# 5V-3_3VSupply_USB.net
KiCad netlist of a schematic drawn in EAGLE
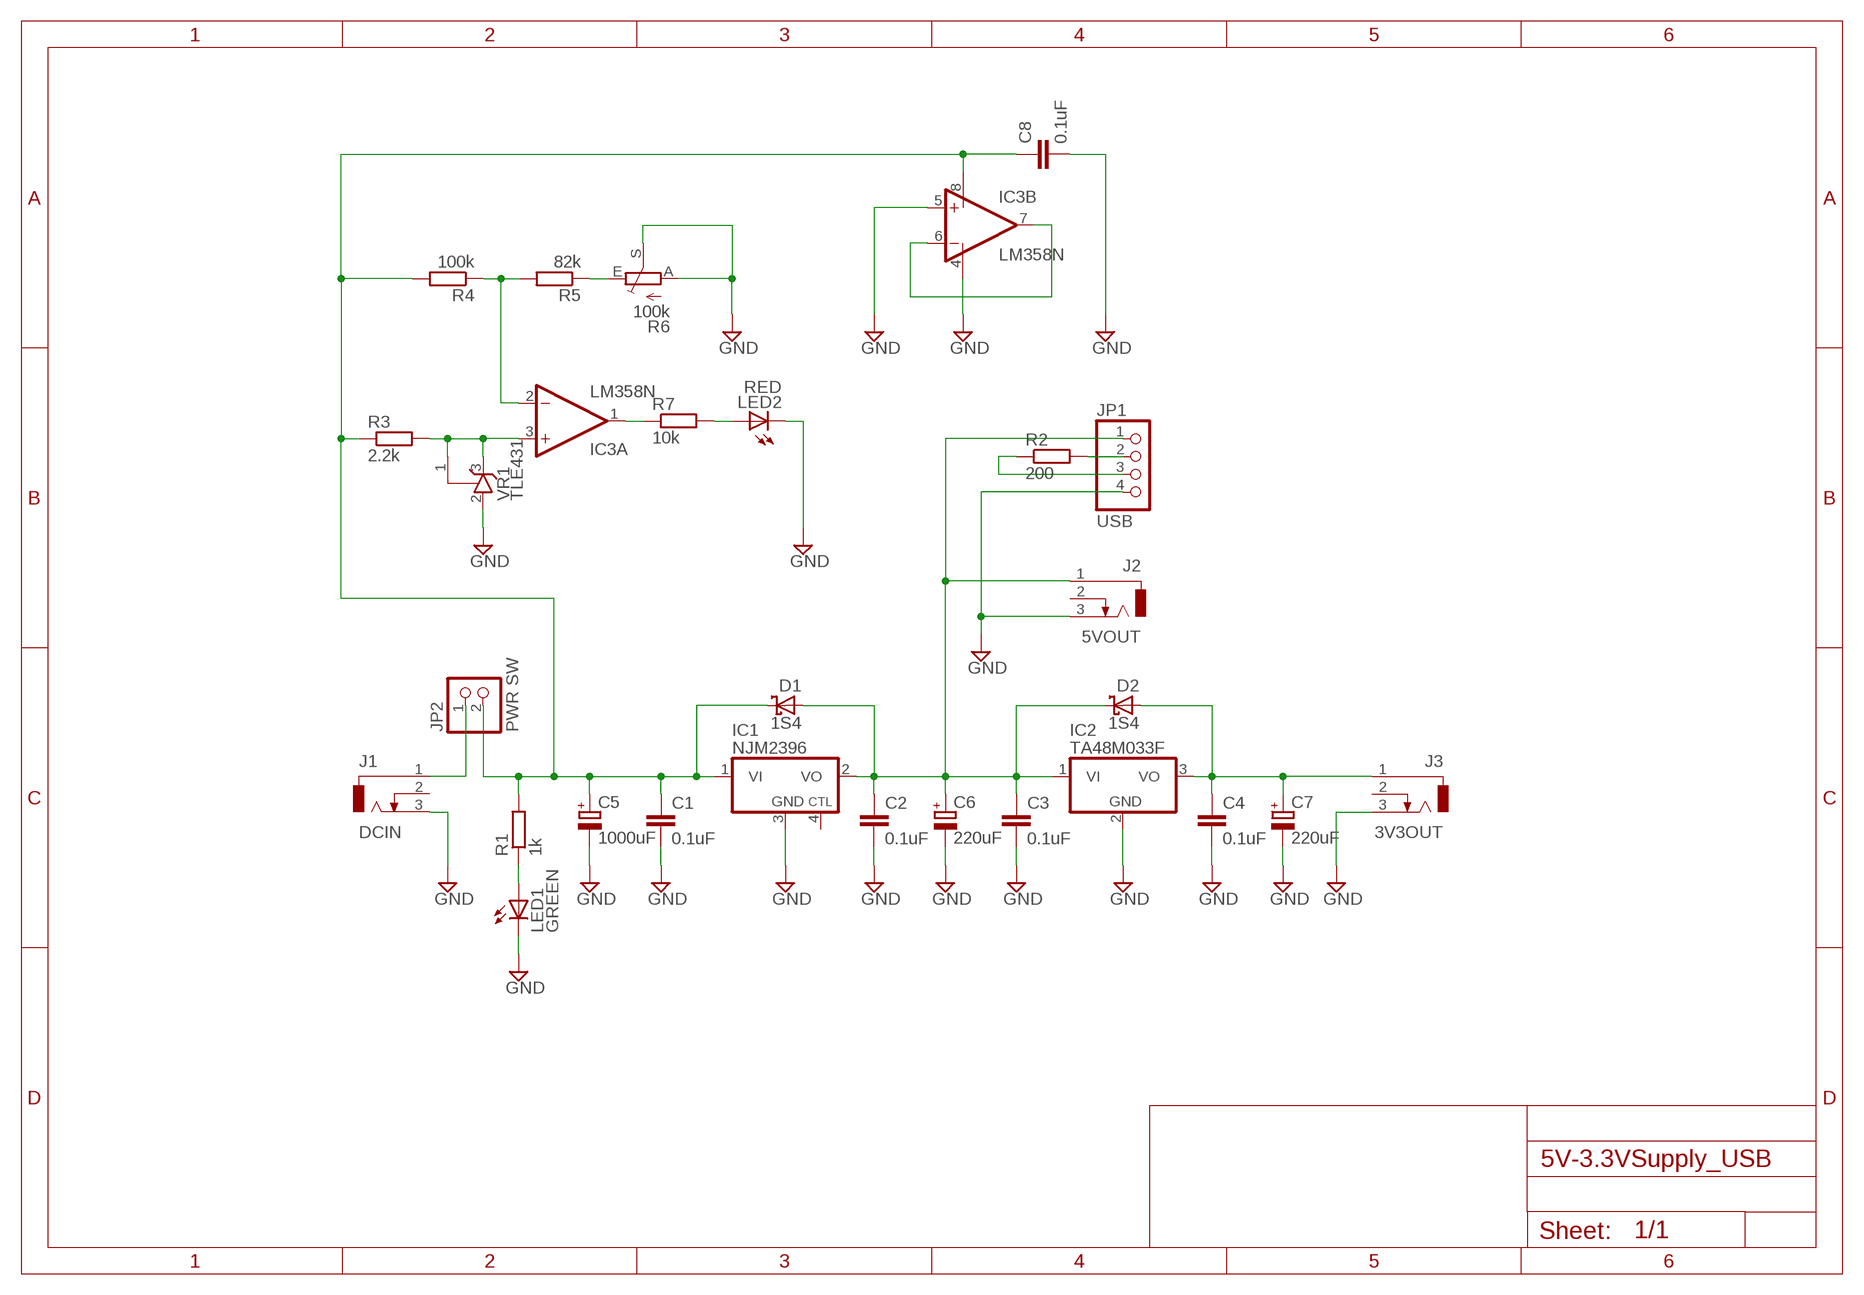
[diagram p0: schematic, sheet 1]

(export (version "E")
  (design (tool "Eeschema 10.0.6"))
  (components
    (comp (ref "C1")
      (value "0.1uF")
      (footprint "eagle-import:C025-024X044")
      (libsource (lib "eagle-import") (part "C-EU025-024X044"))
    )
    (comp (ref "C2")
      (value "0.1uF")
      (footprint "eagle-import:C025-024X044")
      (libsource (lib "eagle-import") (part "C-EU025-024X044"))
    )
    (comp (ref "C3")
      (value "0.1uF")
      (footprint "eagle-import:C025-024X044")
      (libsource (lib "eagle-import") (part "C-EU025-024X044"))
    )
    (comp (ref "C4")
      (value "0.1uF")
      (footprint "eagle-import:C025-024X044")
      (libsource (lib "eagle-import") (part "C-EU025-024X044"))
    )
    (comp (ref "C5")
      (value "1000uF")
      (footprint "eagle-import:TT5D11L")
      (libsource (lib "eagle-import") (part "CPOL-EUTT5D11L"))
    )
    (comp (ref "C6")
      (value "220uF")
      (footprint "eagle-import:E5-8,5")
      (libsource (lib "eagle-import") (part "CPOL-EUE5-8.5"))
    )
    (comp (ref "C7")
      (value "220uF")
      (footprint "eagle-import:E5-8,5")
      (libsource (lib "eagle-import") (part "CPOL-EUE5-8.5"))
    )
    (comp (ref "C8")
      (value "0.1uF")
      (footprint "eagle-import:C025-024X044")
      (libsource (lib "eagle-import") (part "C-EU025-024X044"))
    )
    (comp (ref "D1")
      (value "1S4")
      (footprint "eagle-import:DO41-7.6")
      (libsource (lib "eagle-import") (part "1N5817-B"))
    )
    (comp (ref "D2")
      (value "1S4")
      (footprint "eagle-import:DO41-7.6")
      (libsource (lib "eagle-import") (part "1N5817-B"))
    )
    (comp (ref "IC1")
      (value "NJM2396")
      (footprint "eagle-import:TO220-4H")
      (libsource (lib "eagle-import") (part "NJM2396"))
    )
    (comp (ref "IC2")
      (value "TA48M033F")
      (footprint "eagle-import:TO220V")
      (libsource (lib "eagle-import") (part "78TV05"))
    )
    (comp (ref "IC3")
      (value "LM358N")
      (footprint "eagle-import:DIL08")
      (libsource (lib "eagle-import") (part "LM358N"))
    )
    (comp (ref "J1")
      (value "DCIN")
      (footprint "eagle-import:DCJ0303")
      (libsource (lib "eagle-import") (part "DCJ0303"))
    )
    (comp (ref "J2")
      (value "5VOUT")
      (footprint "eagle-import:DCJ0303")
      (libsource (lib "eagle-import") (part "DCJ0303"))
    )
    (comp (ref "J3")
      (value "3V3OUT")
      (footprint "eagle-import:DCJ0303")
      (libsource (lib "eagle-import") (part "DCJ0303"))
    )
    (comp (ref "JP1")
      (value "USB")
      (footprint "eagle-import:1X04")
      (libsource (lib "eagle-import") (part "PINHD-1X4"))
    )
    (comp (ref "JP2")
      (value "PWR SW")
      (footprint "eagle-import:1X02")
      (libsource (lib "eagle-import") (part "PINHD-1X2"))
    )
    (comp (ref "LED1")
      (value "GREEN")
      (footprint "eagle-import:LED3MM")
      (libsource (lib "eagle-import") (part "LED3MM"))
    )
    (comp (ref "LED2")
      (value "RED")
      (footprint "eagle-import:LED3MM")
      (libsource (lib "eagle-import") (part "LED3MM"))
    )
    (comp (ref "R1")
      (value "1k")
      (footprint "eagle-import:0207_7")
      (libsource (lib "eagle-import") (part "R-EU_0207/7"))
    )
    (comp (ref "R2")
      (value "200")
      (footprint "eagle-import:0207_2V")
      (libsource (lib "eagle-import") (part "R-EU_0207/2V"))
    )
    (comp (ref "R3")
      (value "2.2k")
      (footprint "eagle-import:0207_7")
      (libsource (lib "eagle-import") (part "R-EU_0207/7"))
    )
    (comp (ref "R4")
      (value "100k")
      (footprint "eagle-import:0207_7")
      (libsource (lib "eagle-import") (part "R-EU_0207/7"))
    )
    (comp (ref "R5")
      (value "82k")
      (footprint "eagle-import:0207_7")
      (libsource (lib "eagle-import") (part "R-EU_0207/7"))
    )
    (comp (ref "R6")
      (value "100k")
      (footprint "eagle-import:CT6")
      (libsource (lib "eagle-import") (part "TRIM_EU-CT6"))
    )
    (comp (ref "R7")
      (value "10k")
      (footprint "eagle-import:0207_7")
      (libsource (lib "eagle-import") (part "R-EU_0207/7"))
    )
    (comp (ref "VR1")
      (value "TLE431")
      (footprint "eagle-import:TO226AA")
      (libsource (lib "eagle-import") (part "TL431-INLINE"))
    )
  )
  (nets
    (net (code "1") (name "GND") (class "Default")
      (node (ref "C1") (pin "2") (pinfunction "2_2") (pintype "passive"))
      (node (ref "C2") (pin "2") (pinfunction "2_2") (pintype "passive"))
      (node (ref "C3") (pin "2") (pinfunction "2_2") (pintype "passive"))
      (node (ref "C4") (pin "2") (pinfunction "2_2") (pintype "passive"))
      (node (ref "C5") (pin "-") (pinfunction "-_-") (pintype "passive"))
      (node (ref "C6") (pin "-") (pinfunction "-_-") (pintype "passive"))
      (node (ref "C7") (pin "-") (pinfunction "-_-") (pintype "passive"))
      (node (ref "C8") (pin "2") (pinfunction "2_2") (pintype "passive"))
      (node (ref "IC1") (pin "3") (pinfunction "GND_3") (pintype "passive"))
      (node (ref "IC2") (pin "2") (pinfunction "GND_2") (pintype "passive"))
      (node (ref "IC3") (pin "4") (pinfunction "V-_4") (pintype "power_in"))
      (node (ref "IC3") (pin "5") (pinfunction "+IN_5") (pintype "input"))
      (node (ref "J1") (pin "3") (pinfunction "3_3") (pintype "passive"))
      (node (ref "J2") (pin "3") (pinfunction "3_3") (pintype "passive"))
      (node (ref "J3") (pin "3") (pinfunction "3_3") (pintype "passive"))
      (node (ref "JP1") (pin "4") (pinfunction "4_4") (pintype "passive"))
      (node (ref "LED1") (pin "K") (pinfunction "C_K") (pintype "passive"))
      (node (ref "LED2") (pin "K") (pinfunction "C_K") (pintype "passive"))
      (node (ref "R6") (pin "A") (pinfunction "A_A") (pintype "passive"))
      (node (ref "R6") (pin "S") (pinfunction "S_S") (pintype "passive"))
      (node (ref "VR1") (pin "2") (pinfunction "A_2") (pintype "passive"))
    )
    (net (code "2") (name "Net-(IC1-VI)") (class "Default")
      (node (ref "C1") (pin "1") (pinfunction "1_1") (pintype "passive"))
      (node (ref "C5") (pin "+") (pinfunction "+_+") (pintype "passive"))
      (node (ref "C8") (pin "1") (pinfunction "1_1") (pintype "passive"))
      (node (ref "D1") (pin "C") (pinfunction "C_C") (pintype "passive"))
      (node (ref "IC1") (pin "1") (pinfunction "VI_1") (pintype "input"))
      (node (ref "IC3") (pin "8") (pinfunction "V+_8") (pintype "power_in"))
      (node (ref "JP2") (pin "2") (pinfunction "2_2") (pintype "passive"))
      (node (ref "R1") (pin "2") (pinfunction "2_2") (pintype "passive"))
      (node (ref "R3") (pin "1") (pinfunction "1_1") (pintype "passive"))
      (node (ref "R4") (pin "2") (pinfunction "2_2") (pintype "passive"))
    )
    (net (code "3") (name "Net-(IC1-VO)") (class "Default")
      (node (ref "C2") (pin "1") (pinfunction "1_1") (pintype "passive"))
      (node (ref "C3") (pin "1") (pinfunction "1_1") (pintype "passive"))
      (node (ref "C6") (pin "+") (pinfunction "+_+") (pintype "passive"))
      (node (ref "D1") (pin "A") (pinfunction "A_A") (pintype "passive"))
      (node (ref "D2") (pin "C") (pinfunction "C_C") (pintype "passive"))
      (node (ref "IC1") (pin "2") (pinfunction "VO_2") (pintype "passive"))
      (node (ref "IC2") (pin "1") (pinfunction "VI_1") (pintype "input"))
      (node (ref "J2") (pin "1") (pinfunction "1_1") (pintype "passive"))
      (node (ref "JP1") (pin "1") (pinfunction "1_1") (pintype "passive"))
    )
    (net (code "4") (name "Net-(IC2-VO)") (class "Default")
      (node (ref "C4") (pin "1") (pinfunction "1_1") (pintype "passive"))
      (node (ref "C7") (pin "+") (pinfunction "+_+") (pintype "passive"))
      (node (ref "D2") (pin "A") (pinfunction "A_A") (pintype "passive"))
      (node (ref "IC2") (pin "3") (pinfunction "VO_3") (pintype "passive"))
      (node (ref "J3") (pin "1") (pinfunction "1_1") (pintype "passive"))
    )
    (net (code "5") (name "Net-(IC3A-+IN)") (class "Default")
      (node (ref "IC3") (pin "3") (pinfunction "+IN_3") (pintype "input"))
      (node (ref "R3") (pin "2") (pinfunction "2_2") (pintype "passive"))
      (node (ref "VR1") (pin "1") (pinfunction "R_1") (pintype "passive"))
      (node (ref "VR1") (pin "3") (pinfunction "C_3") (pintype "passive"))
    )
    (net (code "6") (name "Net-(IC3A--IN)") (class "Default")
      (node (ref "IC3") (pin "2") (pinfunction "-IN_2") (pintype "input"))
      (node (ref "R4") (pin "1") (pinfunction "1_1") (pintype "passive"))
      (node (ref "R5") (pin "2") (pinfunction "2_2") (pintype "passive"))
    )
    (net (code "7") (name "Net-(IC3A-OUT)") (class "Default")
      (node (ref "IC3") (pin "1") (pinfunction "OUT_1") (pintype "output"))
      (node (ref "R7") (pin "1") (pinfunction "1_1") (pintype "passive"))
    )
    (net (code "8") (name "Net-(IC3B--IN)") (class "Default")
      (node (ref "IC3") (pin "6") (pinfunction "-IN_6") (pintype "input"))
      (node (ref "IC3") (pin "7") (pinfunction "OUT_7") (pintype "output"))
    )
    (net (code "9") (name "Net-(J1-Pad1)") (class "Default")
      (node (ref "J1") (pin "1") (pinfunction "1_1") (pintype "passive"))
      (node (ref "JP2") (pin "1") (pinfunction "1_1") (pintype "passive"))
    )
    (net (code "10") (name "Net-(JP1-Pad2)") (class "Default")
      (node (ref "JP1") (pin "2") (pinfunction "2_2") (pintype "passive"))
      (node (ref "R2") (pin "2") (pinfunction "2_2") (pintype "passive"))
    )
    (net (code "11") (name "Net-(JP1-Pad3)") (class "Default")
      (node (ref "JP1") (pin "3") (pinfunction "3_3") (pintype "passive"))
      (node (ref "R2") (pin "1") (pinfunction "1_1") (pintype "passive"))
    )
    (net (code "12") (name "Net-(LED1-PadA)") (class "Default")
      (node (ref "LED1") (pin "A") (pinfunction "A_A") (pintype "passive"))
      (node (ref "R1") (pin "1") (pinfunction "1_1") (pintype "passive"))
    )
    (net (code "13") (name "Net-(LED2-PadA)") (class "Default")
      (node (ref "LED2") (pin "A") (pinfunction "A_A") (pintype "passive"))
      (node (ref "R7") (pin "2") (pinfunction "2_2") (pintype "passive"))
    )
    (net (code "14") (name "Net-(R5-Pad1)") (class "Default")
      (node (ref "R5") (pin "1") (pinfunction "1_1") (pintype "passive"))
      (node (ref "R6") (pin "E") (pinfunction "E_E") (pintype "passive"))
    )
    (net (code "15") (name "unconnected-(IC1-CTL-Pad4)") (class "Default")
      (node (ref "IC1") (pin "4") (pinfunction "CTL_4") (pintype "passive"))
    )
    (net (code "16") (name "unconnected-(J1-Pad2)") (class "Default")
      (node (ref "J1") (pin "2") (pinfunction "2_2") (pintype "passive"))
    )
    (net (code "17") (name "unconnected-(J2-Pad2)") (class "Default")
      (node (ref "J2") (pin "2") (pinfunction "2_2") (pintype "passive"))
    )
    (net (code "18") (name "unconnected-(J3-Pad2)") (class "Default")
      (node (ref "J3") (pin "2") (pinfunction "2_2") (pintype "passive"))
    )
  )
)
